# servo_driver.net
KiCad netlist of a schematic drawn in EAGLE
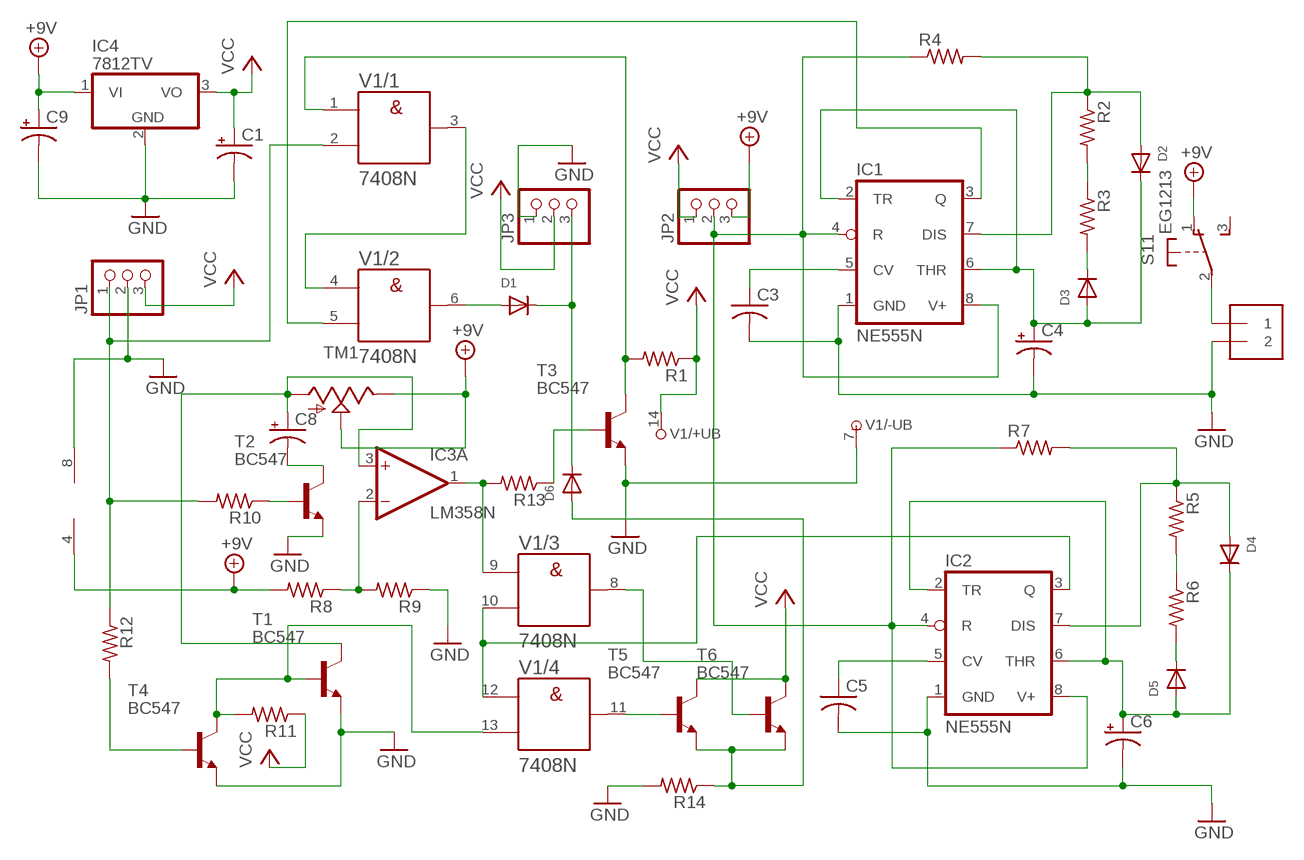
[diagram p0: schematic, sheet 1]

(export (version "E")
  (design (tool "Eeschema 10.0.6"))
  (components
    (comp (ref "C1")
      (value "CPOL-USE2-4")
      (footprint "eagle-import:E2-4")
      (libsource (lib "eagle-import") (part "CPOL-USE2-4"))
    )
    (comp (ref "C3")
      (value "C-US025-030X050")
      (footprint "eagle-import:C025-030X050")
      (libsource (lib "eagle-import") (part "C-US025-030X050"))
    )
    (comp (ref "C4")
      (value "CPOL-USE2-4")
      (footprint "eagle-import:E2-4")
      (libsource (lib "eagle-import") (part "CPOL-USE2-4"))
    )
    (comp (ref "C5")
      (value "C-US025-030X050")
      (footprint "eagle-import:C025-030X050")
      (libsource (lib "eagle-import") (part "C-US025-030X050"))
    )
    (comp (ref "C6")
      (value "CPOL-USE2-4")
      (footprint "eagle-import:E2-4")
      (libsource (lib "eagle-import") (part "CPOL-USE2-4"))
    )
    (comp (ref "C8")
      (value "CPOL-USE2.5-6")
      (footprint "eagle-import:E2,5-6")
      (libsource (lib "eagle-import") (part "CPOL-USE2.5-6"))
    )
    (comp (ref "C9")
      (value "CPOL-USE2.5-6")
      (footprint "eagle-import:E2,5-6")
      (libsource (lib "eagle-import") (part "CPOL-USE2.5-6"))
    )
    (comp (ref "D1")
      (value "DIODEDO-1N4148")
      (footprint "eagle-import:DO-1N4148")
      (libsource (lib "eagle-import") (part "DIODEDO-1N4148"))
    )
    (comp (ref "D2")
      (value "DIODEDO-1N4148")
      (footprint "eagle-import:DO-1N4148")
      (libsource (lib "eagle-import") (part "DIODEDO-1N4148"))
    )
    (comp (ref "D3")
      (value "DIODEDO-1N4148")
      (footprint "eagle-import:DO-1N4148")
      (libsource (lib "eagle-import") (part "DIODEDO-1N4148"))
    )
    (comp (ref "D4")
      (value "DIODEDO-1N4148")
      (footprint "eagle-import:DO-1N4148")
      (libsource (lib "eagle-import") (part "DIODEDO-1N4148"))
    )
    (comp (ref "D5")
      (value "DIODEDO-1N4148")
      (footprint "eagle-import:DO-1N4148")
      (libsource (lib "eagle-import") (part "DIODEDO-1N4148"))
    )
    (comp (ref "D6")
      (value "DIODEDO-1N4148")
      (footprint "eagle-import:DO-1N4148")
      (libsource (lib "eagle-import") (part "DIODEDO-1N4148"))
    )
    (comp (ref "IC1")
      (value "NE555N")
      (footprint "eagle-import:DIL08-ROUND")
      (libsource (lib "eagle-import") (part "555NNE"))
    )
    (comp (ref "IC2")
      (value "NE555N")
      (footprint "eagle-import:DIL08-ROUND")
      (libsource (lib "eagle-import") (part "555NNE"))
    )
    (comp (ref "IC3")
      (value "LM358N")
      (footprint "eagle-import:DIL08")
      (libsource (lib "eagle-import") (part "LM358N"))
    )
    (comp (ref "IC4")
      (value "7812TV")
      (footprint "eagle-import:TO220V")
      (libsource (lib "eagle-import") (part "78TV12"))
    )
    (comp (ref "J1")
      (value "1X2-3.5MM")
      (footprint "eagle-import:1X2-3.5MM")
      (libsource (lib "eagle-import") (part "1X2-3.5MM"))
    )
    (comp (ref "JP1")
      (value "PINHD-1X3")
      (footprint "eagle-import:1X03")
      (libsource (lib "eagle-import") (part "PINHD-1X3"))
    )
    (comp (ref "JP2")
      (value "PINHD-1X3")
      (footprint "eagle-import:1X03")
      (libsource (lib "eagle-import") (part "PINHD-1X3"))
    )
    (comp (ref "JP3")
      (value "PINHD-1X3")
      (footprint "eagle-import:1X03")
      (libsource (lib "eagle-import") (part "PINHD-1X3"))
    )
    (comp (ref "R1")
      (value "R-US_0207/9")
      (footprint "eagle-import:0207_9")
      (libsource (lib "eagle-import") (part "R-US_0207/9"))
    )
    (comp (ref "R2")
      (value "R-US_0207/9")
      (footprint "eagle-import:0207_9")
      (libsource (lib "eagle-import") (part "R-US_0207/9"))
    )
    (comp (ref "R3")
      (value "R-US_0207/9")
      (footprint "eagle-import:0207_9")
      (libsource (lib "eagle-import") (part "R-US_0207/9"))
    )
    (comp (ref "R4")
      (value "R-US_0207/9")
      (footprint "eagle-import:0207_9")
      (libsource (lib "eagle-import") (part "R-US_0207/9"))
    )
    (comp (ref "R5")
      (value "R-US_0207/9")
      (footprint "eagle-import:0207_9")
      (libsource (lib "eagle-import") (part "R-US_0207/9"))
    )
    (comp (ref "R6")
      (value "R-US_0207/9")
      (footprint "eagle-import:0207_9")
      (libsource (lib "eagle-import") (part "R-US_0207/9"))
    )
    (comp (ref "R7")
      (value "R-US_0207/9")
      (footprint "eagle-import:0207_9")
      (libsource (lib "eagle-import") (part "R-US_0207/9"))
    )
    (comp (ref "R8")
      (value "R-US_0207/9")
      (footprint "eagle-import:0207_9")
      (libsource (lib "eagle-import") (part "R-US_0207/9"))
    )
    (comp (ref "R9")
      (value "R-US_0207/9")
      (footprint "eagle-import:0207_9")
      (libsource (lib "eagle-import") (part "R-US_0207/9"))
    )
    (comp (ref "R10")
      (value "R-US_0207/9")
      (footprint "eagle-import:0207_9")
      (libsource (lib "eagle-import") (part "R-US_0207/9"))
    )
    (comp (ref "R11")
      (value "R-US_0207/9")
      (footprint "eagle-import:0207_9")
      (libsource (lib "eagle-import") (part "R-US_0207/9"))
    )
    (comp (ref "R12")
      (value "R-US_0207/9")
      (footprint "eagle-import:0207_9")
      (libsource (lib "eagle-import") (part "R-US_0207/9"))
    )
    (comp (ref "R13")
      (value "R-US_0207/9")
      (footprint "eagle-import:0207_9")
      (libsource (lib "eagle-import") (part "R-US_0207/9"))
    )
    (comp (ref "R14")
      (value "R-US_0207/9")
      (footprint "eagle-import:0207_9")
      (libsource (lib "eagle-import") (part "R-US_0207/9"))
    )
    (comp (ref "S1")
      (value "EG1213")
      (footprint "eagle-import:EG1213")
      (libsource (lib "eagle-import") (part "EG1213"))
    )
    (comp (ref "T1")
      (value "BC547")
      (footprint "eagle-import:TO92")
      (libsource (lib "eagle-import") (part "BC547"))
    )
    (comp (ref "T2")
      (value "BC547")
      (footprint "eagle-import:TO92")
      (libsource (lib "eagle-import") (part "BC547"))
    )
    (comp (ref "T3")
      (value "BC547")
      (footprint "eagle-import:TO92")
      (libsource (lib "eagle-import") (part "BC547"))
    )
    (comp (ref "T4")
      (value "BC547")
      (footprint "eagle-import:TO92")
      (libsource (lib "eagle-import") (part "BC547"))
    )
    (comp (ref "T5")
      (value "BC547")
      (footprint "eagle-import:TO92")
      (libsource (lib "eagle-import") (part "BC547"))
    )
    (comp (ref "T6")
      (value "BC547")
      (footprint "eagle-import:TO92")
      (libsource (lib "eagle-import") (part "BC547"))
    )
    (comp (ref "TM1")
      (value "TRIM")
      (footprint "eagle-import:6MM")
      (libsource (lib "eagle-import") (part "TRIM"))
    )
    (comp (ref "V1")
      (value "7408N")
      (footprint "eagle-import:DIL14")
      (libsource (lib "eagle-import") (part "7408N"))
    )
  )
  (nets
    (net (code "1") (name "+9V") (class "Default")
      (node (ref "C9") (pin "+") (pinfunction "+_+") (pintype "passive"))
      (node (ref "IC3") (pin "4") (pinfunction "V-_4") (pintype "power_in"))
      (node (ref "IC4") (pin "1") (pinfunction "VI_1") (pintype "input"))
      (node (ref "JP2") (pin "3") (pinfunction "3_3") (pintype "passive"))
      (node (ref "R8") (pin "2") (pinfunction "2_2") (pintype "passive"))
      (node (ref "S1") (pin "1") (pinfunction "O_1") (pintype "passive"))
      (node (ref "TM1") (pin "E") (pinfunction "E_E") (pintype "passive"))
      (node (ref "TM1") (pin "S") (pinfunction "S_S") (pintype "passive"))
    )
    (net (code "2") (name "GND") (class "Default")
      (node (ref "C1") (pin "-") (pinfunction "-_-") (pintype "passive"))
      (node (ref "C3") (pin "2") (pinfunction "2_2") (pintype "passive"))
      (node (ref "C4") (pin "-") (pinfunction "-_-") (pintype "passive"))
      (node (ref "C5") (pin "2") (pinfunction "2_2") (pintype "passive"))
      (node (ref "C6") (pin "-") (pinfunction "-_-") (pintype "passive"))
      (node (ref "C9") (pin "-") (pinfunction "-_-") (pintype "passive"))
      (node (ref "IC1") (pin "1") (pinfunction "GND_1") (pintype "power_in"))
      (node (ref "IC2") (pin "1") (pinfunction "GND_1") (pintype "power_in"))
      (node (ref "IC3") (pin "8") (pinfunction "V+_8") (pintype "power_in"))
      (node (ref "IC4") (pin "2") (pinfunction "GND_2") (pintype "passive"))
      (node (ref "J1") (pin "2") (pinfunction "2_2") (pintype "passive"))
      (node (ref "JP1") (pin "2") (pinfunction "2_2") (pintype "passive"))
      (node (ref "JP3") (pin "1") (pinfunction "1_1") (pintype "passive"))
      (node (ref "R14") (pin "2") (pinfunction "2_2") (pintype "passive"))
      (node (ref "R9") (pin "1") (pinfunction "1_1") (pintype "passive"))
      (node (ref "T1") (pin "1") (pinfunction "E_1") (pintype "passive"))
      (node (ref "T2") (pin "1") (pinfunction "E_1") (pintype "passive"))
      (node (ref "T3") (pin "1") (pinfunction "E_1") (pintype "passive"))
      (node (ref "T4") (pin "1") (pinfunction "E_1") (pintype "passive"))
      (node (ref "V1") (pin "7") (pinfunction "-UB_7") (pintype "power_in"))
    )
    (net (code "3") (name "Net-(D1-PadC)") (class "Default")
      (node (ref "D1") (pin "C") (pinfunction "C_C") (pintype "passive"))
      (node (ref "D6") (pin "C") (pinfunction "C_C") (pintype "passive"))
      (node (ref "JP3") (pin "3") (pinfunction "3_3") (pintype "passive"))
    )
    (net (code "4") (name "Net-(D3-PadC)") (class "Default")
      (node (ref "D3") (pin "C") (pinfunction "C_C") (pintype "passive"))
      (node (ref "R3") (pin "2") (pinfunction "2_2") (pintype "passive"))
    )
    (net (code "5") (name "Net-(D5-PadC)") (class "Default")
      (node (ref "D5") (pin "C") (pinfunction "C_C") (pintype "passive"))
      (node (ref "R6") (pin "2") (pinfunction "2_2") (pintype "passive"))
    )
    (net (code "6") (name "Net-(IC1-CV)") (class "Default")
      (node (ref "C3") (pin "1") (pinfunction "1_1") (pintype "passive"))
      (node (ref "IC1") (pin "5") (pinfunction "CV_5") (pintype "input"))
    )
    (net (code "7") (name "Net-(IC1-DIS)") (class "Default")
      (node (ref "D2") (pin "A") (pinfunction "A_A") (pintype "passive"))
      (node (ref "IC1") (pin "7") (pinfunction "DIS_7") (pintype "input"))
      (node (ref "R2") (pin "1") (pinfunction "1_1") (pintype "passive"))
      (node (ref "R4") (pin "2") (pinfunction "2_2") (pintype "passive"))
    )
    (net (code "8") (name "Net-(IC1-Q)") (class "Default")
      (node (ref "IC1") (pin "3") (pinfunction "Q_3") (pintype "output"))
      (node (ref "V1") (pin "5") (pinfunction "B_5") (pintype "input"))
    )
    (net (code "9") (name "Net-(IC1-R)") (class "Default")
      (node (ref "IC1") (pin "4") (pinfunction "R_4") (pintype "input"))
      (node (ref "IC1") (pin "8") (pinfunction "V+_8") (pintype "power_in"))
      (node (ref "IC2") (pin "4") (pinfunction "R_4") (pintype "input"))
      (node (ref "IC2") (pin "8") (pinfunction "V+_8") (pintype "power_in"))
      (node (ref "JP2") (pin "2") (pinfunction "2_2") (pintype "passive"))
      (node (ref "R4") (pin "1") (pinfunction "1_1") (pintype "passive"))
      (node (ref "R7") (pin "1") (pinfunction "1_1") (pintype "passive"))
    )
    (net (code "10") (name "Net-(IC1-THR)") (class "Default")
      (node (ref "C4") (pin "+") (pinfunction "+_+") (pintype "passive"))
      (node (ref "D2") (pin "C") (pinfunction "C_C") (pintype "passive"))
      (node (ref "D3") (pin "A") (pinfunction "A_A") (pintype "passive"))
      (node (ref "IC1") (pin "2") (pinfunction "TR_2") (pintype "input"))
      (node (ref "IC1") (pin "6") (pinfunction "THR_6") (pintype "input"))
    )
    (net (code "11") (name "Net-(IC2-CV)") (class "Default")
      (node (ref "C5") (pin "1") (pinfunction "1_1") (pintype "passive"))
      (node (ref "IC2") (pin "5") (pinfunction "CV_5") (pintype "input"))
    )
    (net (code "12") (name "Net-(IC2-DIS)") (class "Default")
      (node (ref "D4") (pin "A") (pinfunction "A_A") (pintype "passive"))
      (node (ref "IC2") (pin "7") (pinfunction "DIS_7") (pintype "input"))
      (node (ref "R5") (pin "1") (pinfunction "1_1") (pintype "passive"))
      (node (ref "R7") (pin "2") (pinfunction "2_2") (pintype "passive"))
    )
    (net (code "13") (name "Net-(IC2-Q)") (class "Default")
      (node (ref "IC2") (pin "3") (pinfunction "Q_3") (pintype "output"))
      (node (ref "V1") (pin "10") (pinfunction "B_10") (pintype "input"))
      (node (ref "V1") (pin "12") (pinfunction "A_12") (pintype "input"))
    )
    (net (code "14") (name "Net-(IC2-THR)") (class "Default")
      (node (ref "C6") (pin "+") (pinfunction "+_+") (pintype "passive"))
      (node (ref "D4") (pin "C") (pinfunction "C_C") (pintype "passive"))
      (node (ref "D5") (pin "A") (pinfunction "A_A") (pintype "passive"))
      (node (ref "IC2") (pin "2") (pinfunction "TR_2") (pintype "input"))
      (node (ref "IC2") (pin "6") (pinfunction "THR_6") (pintype "input"))
    )
    (net (code "15") (name "Net-(IC3A-+IN)") (class "Default")
      (node (ref "C8") (pin "+") (pinfunction "+_+") (pintype "passive"))
      (node (ref "IC3") (pin "3") (pinfunction "+IN_3") (pintype "input"))
      (node (ref "T1") (pin "3") (pinfunction "C_3") (pintype "passive"))
      (node (ref "TM1") (pin "A") (pinfunction "A_A") (pintype "passive"))
    )
    (net (code "16") (name "Net-(IC3A--IN)") (class "Default")
      (node (ref "IC3") (pin "2") (pinfunction "-IN_2") (pintype "input"))
      (node (ref "R8") (pin "1") (pinfunction "1_1") (pintype "passive"))
      (node (ref "R9") (pin "2") (pinfunction "2_2") (pintype "passive"))
    )
    (net (code "17") (name "Net-(IC3A-OUT)") (class "Default")
      (node (ref "IC3") (pin "1") (pinfunction "OUT_1") (pintype "output"))
      (node (ref "R13") (pin "2") (pinfunction "2_2") (pintype "passive"))
      (node (ref "V1") (pin "9") (pinfunction "A_9") (pintype "input"))
    )
    (net (code "18") (name "Net-(R2-Pad2)") (class "Default")
      (node (ref "R2") (pin "2") (pinfunction "2_2") (pintype "passive"))
      (node (ref "R3") (pin "1") (pinfunction "1_1") (pintype "passive"))
    )
    (net (code "19") (name "Net-(R5-Pad2)") (class "Default")
      (node (ref "R5") (pin "2") (pinfunction "2_2") (pintype "passive"))
      (node (ref "R6") (pin "1") (pinfunction "1_1") (pintype "passive"))
    )
    (net (code "20") (name "Net-(S1A-P)") (class "Default")
      (node (ref "J1") (pin "1") (pinfunction "1_1") (pintype "passive"))
      (node (ref "S1") (pin "2") (pinfunction "P_2") (pintype "passive"))
    )
    (net (code "21") (name "Net-(T1-B)") (class "Default")
      (node (ref "R11") (pin "2") (pinfunction "2_2") (pintype "passive"))
      (node (ref "T1") (pin "2") (pinfunction "B_2") (pintype "passive"))
      (node (ref "T4") (pin "3") (pinfunction "C_3") (pintype "passive"))
      (node (ref "V1") (pin "13") (pinfunction "B_13") (pintype "input"))
    )
    (net (code "22") (name "Net-(T2-B)") (class "Default")
      (node (ref "R10") (pin "1") (pinfunction "1_1") (pintype "passive"))
      (node (ref "T2") (pin "2") (pinfunction "B_2") (pintype "passive"))
    )
    (net (code "23") (name "Net-(T2-C)") (class "Default")
      (node (ref "C8") (pin "-") (pinfunction "-_-") (pintype "passive"))
      (node (ref "T2") (pin "3") (pinfunction "C_3") (pintype "passive"))
    )
    (net (code "24") (name "Net-(T3-B)") (class "Default")
      (node (ref "R13") (pin "1") (pinfunction "1_1") (pintype "passive"))
      (node (ref "T3") (pin "2") (pinfunction "B_2") (pintype "passive"))
    )
    (net (code "25") (name "Net-(T3-C)") (class "Default")
      (node (ref "R1") (pin "2") (pinfunction "2_2") (pintype "passive"))
      (node (ref "T3") (pin "3") (pinfunction "C_3") (pintype "passive"))
      (node (ref "V1") (pin "1") (pinfunction "A_1") (pintype "input"))
    )
    (net (code "26") (name "Net-(T4-B)") (class "Default")
      (node (ref "R12") (pin "2") (pinfunction "2_2") (pintype "passive"))
      (node (ref "T4") (pin "2") (pinfunction "B_2") (pintype "passive"))
    )
    (net (code "27") (name "Net-(T5-B)") (class "Default")
      (node (ref "T5") (pin "2") (pinfunction "B_2") (pintype "passive"))
      (node (ref "V1") (pin "11") (pinfunction "Y_11") (pintype "output"))
    )
    (net (code "28") (name "Net-(T5-E)") (class "Default")
      (node (ref "D6") (pin "A") (pinfunction "A_A") (pintype "passive"))
      (node (ref "R14") (pin "1") (pinfunction "1_1") (pintype "passive"))
      (node (ref "T5") (pin "1") (pinfunction "E_1") (pintype "passive"))
      (node (ref "T6") (pin "1") (pinfunction "E_1") (pintype "passive"))
    )
    (net (code "29") (name "Net-(T6-B)") (class "Default")
      (node (ref "T6") (pin "2") (pinfunction "B_2") (pintype "passive"))
      (node (ref "V1") (pin "8") (pinfunction "Y_8") (pintype "output"))
    )
    (net (code "30") (name "Net-(V1C-B)") (class "Default")
      (node (ref "JP1") (pin "1") (pinfunction "1_1") (pintype "passive"))
      (node (ref "R10") (pin "2") (pinfunction "2_2") (pintype "passive"))
      (node (ref "R12") (pin "1") (pinfunction "1_1") (pintype "passive"))
      (node (ref "V1") (pin "2") (pinfunction "B_2") (pintype "input"))
    )
    (net (code "31") (name "Net-(V1C-Y)") (class "Default")
      (node (ref "V1") (pin "3") (pinfunction "Y_3") (pintype "output"))
      (node (ref "V1") (pin "4") (pinfunction "A_4") (pintype "input"))
    )
    (net (code "32") (name "Net-(V1D-Y)") (class "Default")
      (node (ref "D1") (pin "A") (pinfunction "A_A") (pintype "passive"))
      (node (ref "V1") (pin "6") (pinfunction "Y_6") (pintype "output"))
    )
    (net (code "33") (name "VCC") (class "Default")
      (node (ref "C1") (pin "+") (pinfunction "+_+") (pintype "passive"))
      (node (ref "IC4") (pin "3") (pinfunction "VO_3") (pintype "passive"))
      (node (ref "JP1") (pin "3") (pinfunction "3_3") (pintype "passive"))
      (node (ref "JP2") (pin "1") (pinfunction "1_1") (pintype "passive"))
      (node (ref "JP3") (pin "2") (pinfunction "2_2") (pintype "passive"))
      (node (ref "R1") (pin "1") (pinfunction "1_1") (pintype "passive"))
      (node (ref "R11") (pin "1") (pinfunction "1_1") (pintype "passive"))
      (node (ref "T5") (pin "3") (pinfunction "C_3") (pintype "passive"))
      (node (ref "T6") (pin "3") (pinfunction "C_3") (pintype "passive"))
      (node (ref "V1") (pin "14") (pinfunction "+UB_14") (pintype "power_in"))
    )
    (net (code "34") (name "unconnected-(S1A-S-Pad3)") (class "Default")
      (node (ref "S1") (pin "3") (pinfunction "S_3") (pintype "passive"))
    )
  )
)
